# VCO.net
KiCad netlist of a schematic drawn in EAGLE
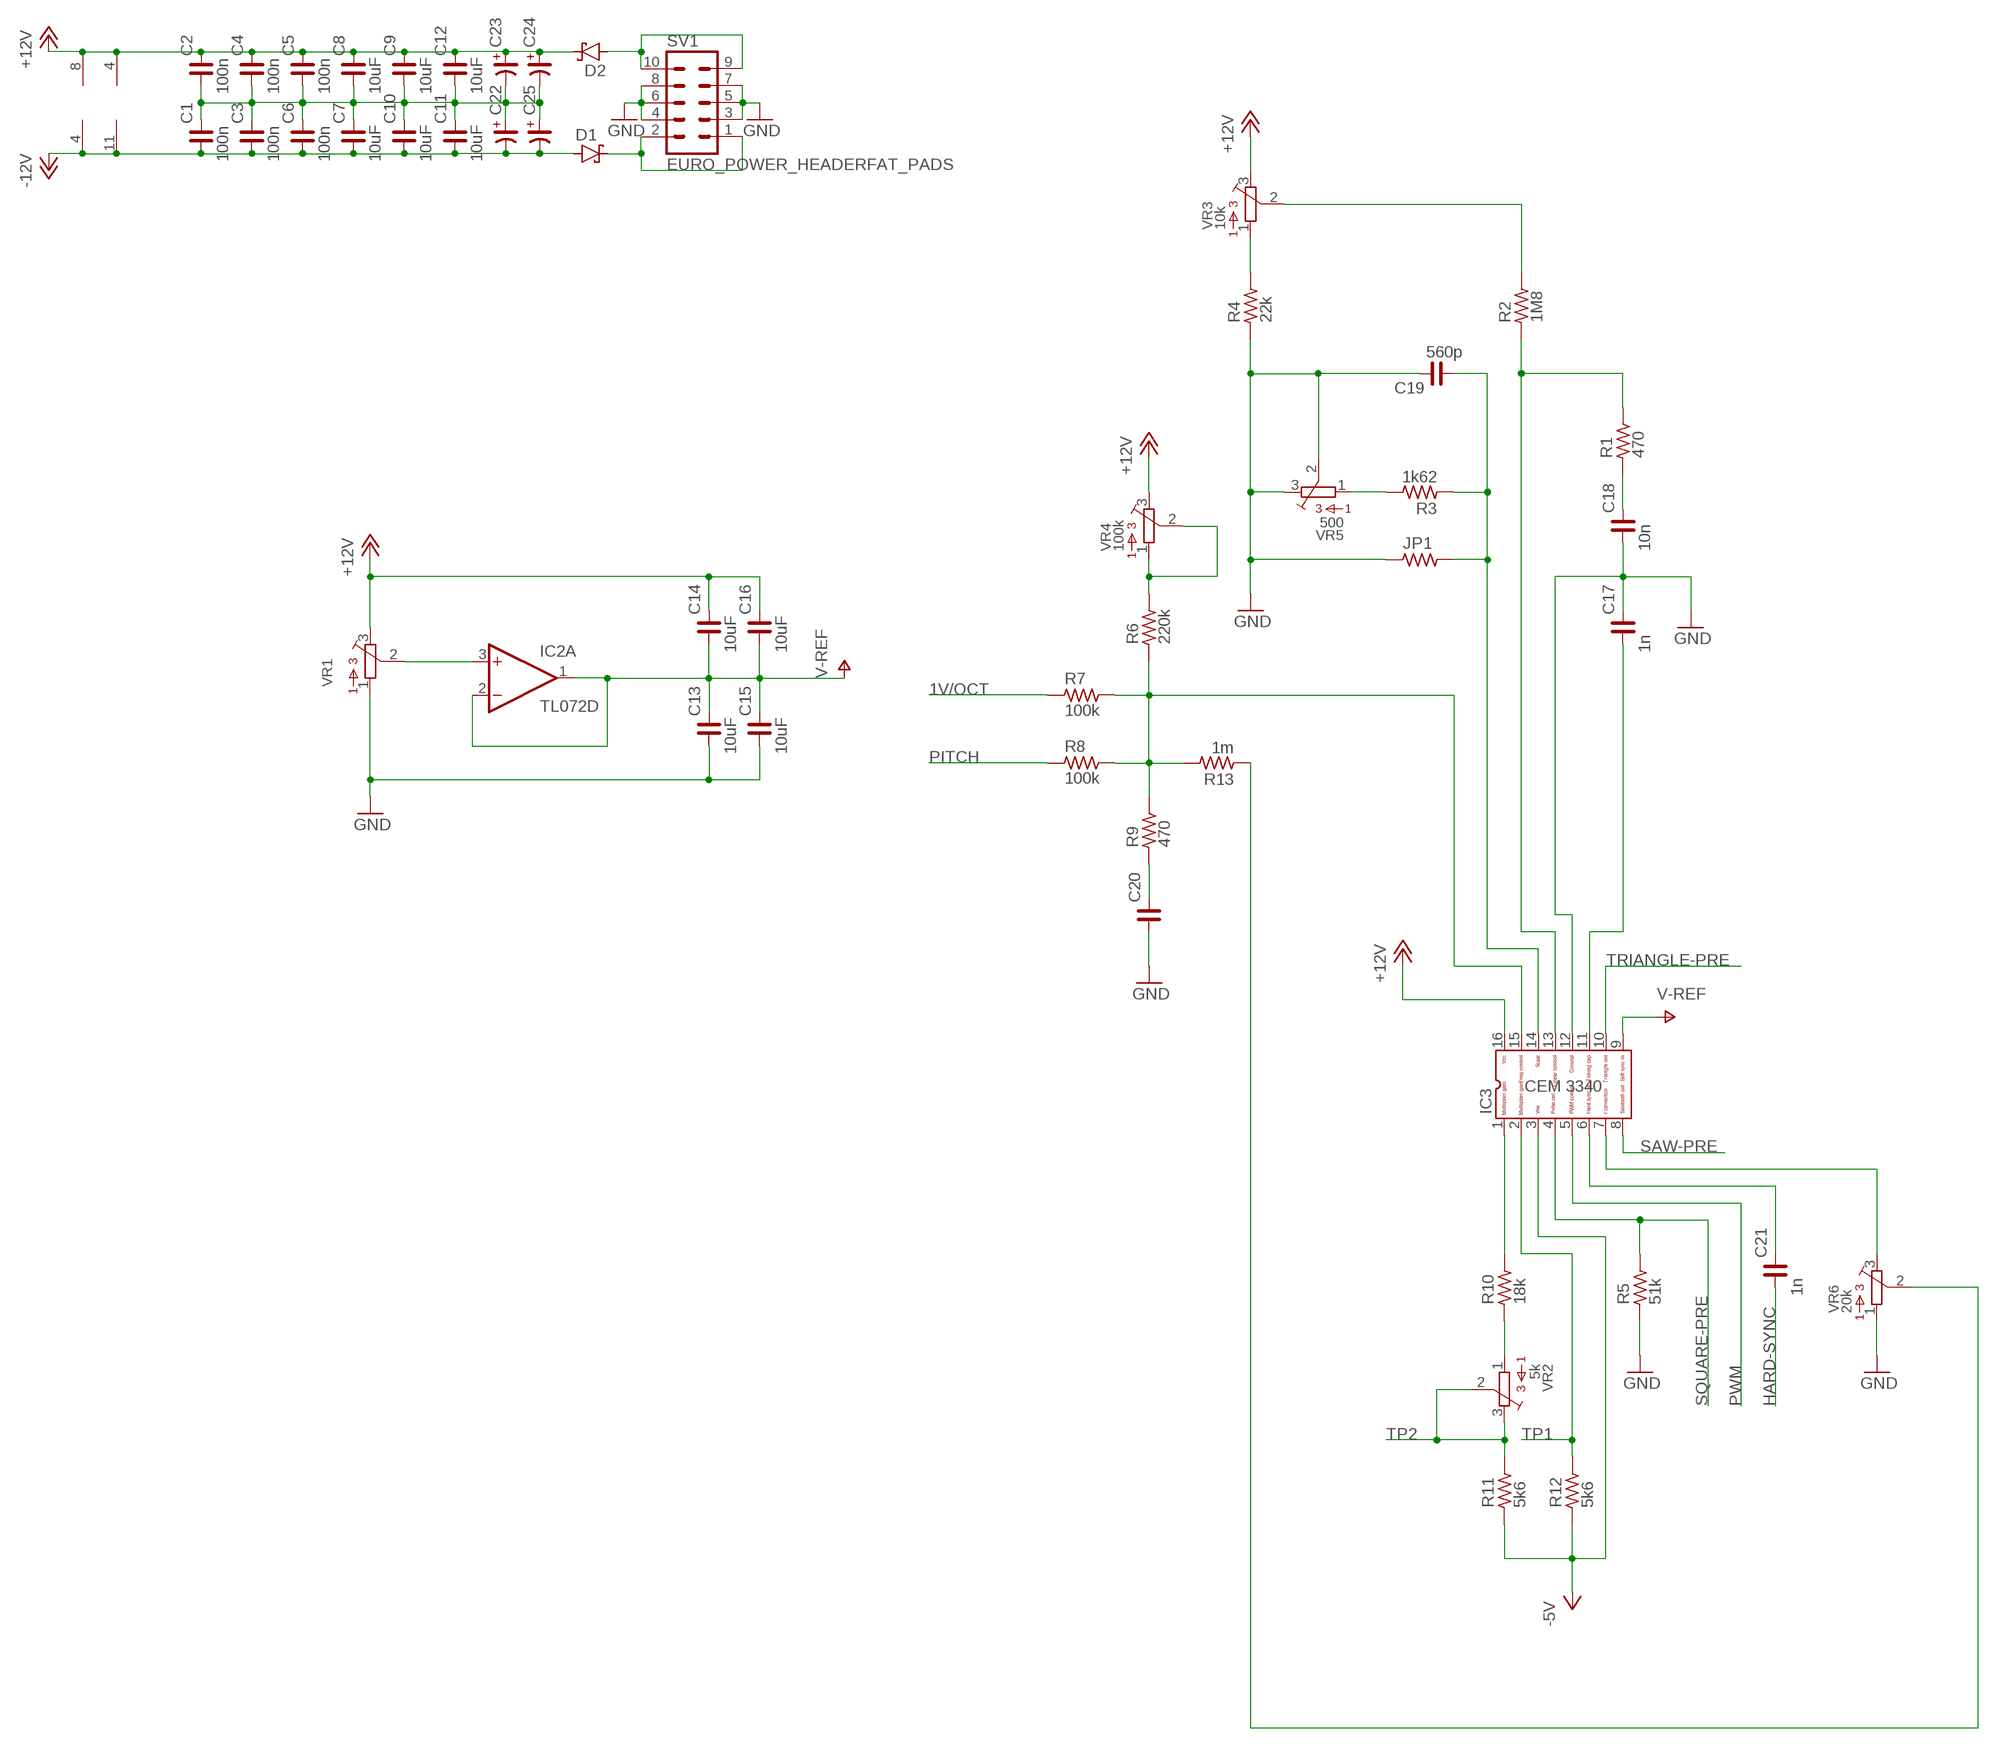
[diagram p0: schematic, sheet 1, part 1 of 2]
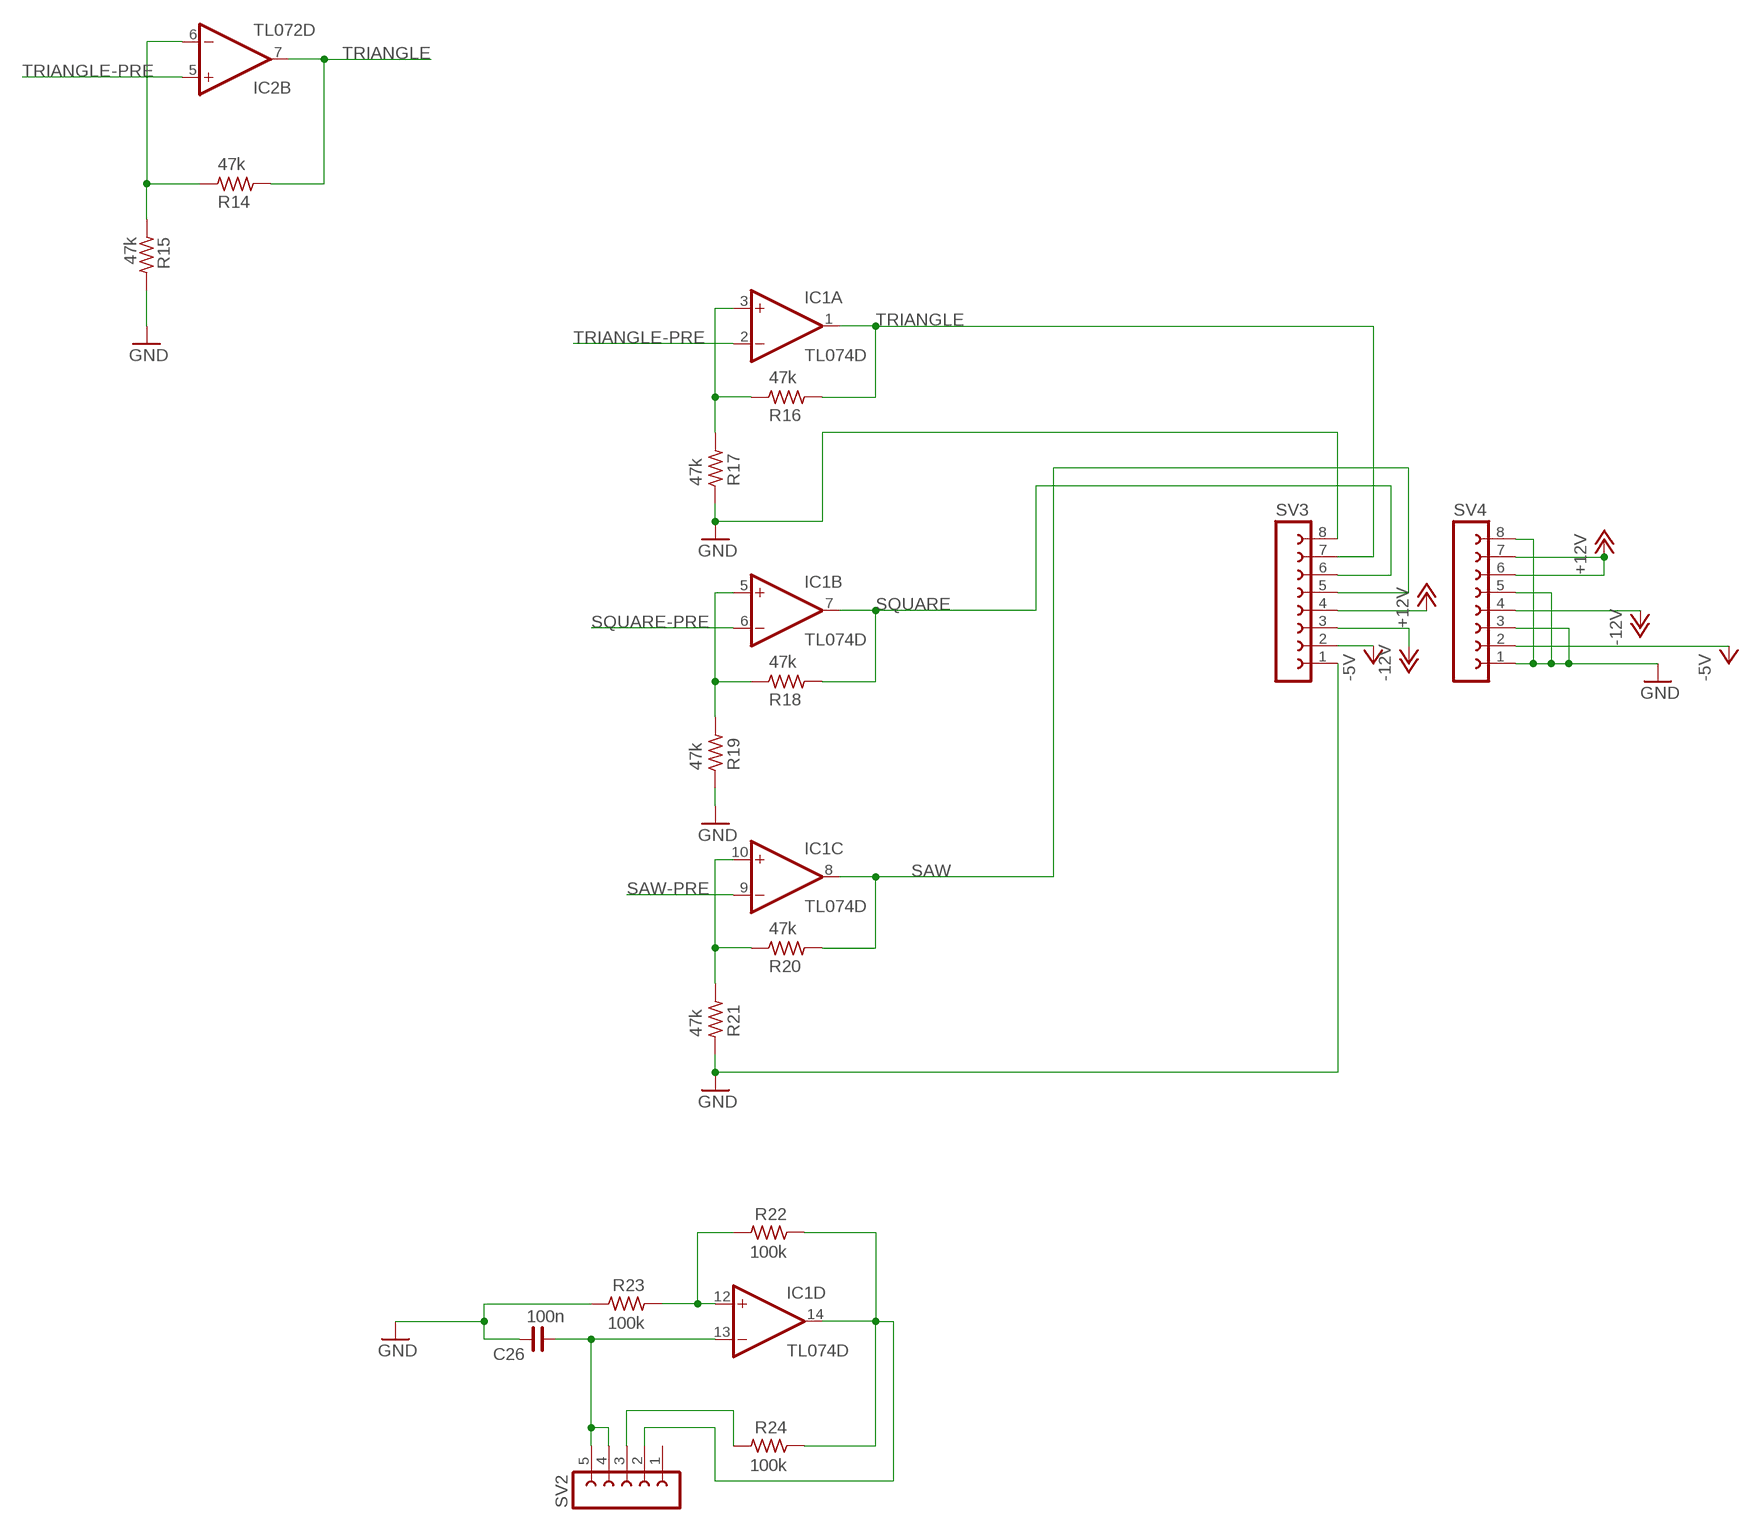
[diagram p1: schematic, sheet 1, part 2 of 2]

(export (version "E")
  (design (tool "Eeschema 10.0.6"))
  (components
    (comp (ref "C1")
      (value "100n")
      (footprint "eagle-import:C0402")
      (libsource (lib "eagle-import") (part "C_0402"))
    )
    (comp (ref "C2")
      (value "100n")
      (footprint "eagle-import:C0402")
      (libsource (lib "eagle-import") (part "C_0402"))
    )
    (comp (ref "C3")
      (value "100n")
      (footprint "eagle-import:C0402")
      (libsource (lib "eagle-import") (part "C_0402"))
    )
    (comp (ref "C4")
      (value "100n")
      (footprint "eagle-import:C0402")
      (libsource (lib "eagle-import") (part "C_0402"))
    )
    (comp (ref "C5")
      (value "100n")
      (footprint "eagle-import:C0402")
      (libsource (lib "eagle-import") (part "C_0402"))
    )
    (comp (ref "C6")
      (value "100n")
      (footprint "eagle-import:C0402")
      (libsource (lib "eagle-import") (part "C_0402"))
    )
    (comp (ref "C7")
      (value "10uF")
      (footprint "eagle-import:C0402")
      (libsource (lib "eagle-import") (part "C_0402"))
    )
    (comp (ref "C8")
      (value "10uF")
      (footprint "eagle-import:C0402")
      (libsource (lib "eagle-import") (part "C_0402"))
    )
    (comp (ref "C9")
      (value "10uF")
      (footprint "eagle-import:C0402")
      (libsource (lib "eagle-import") (part "C_0402"))
    )
    (comp (ref "C10")
      (value "10uF")
      (footprint "eagle-import:C0402")
      (libsource (lib "eagle-import") (part "C_0402"))
    )
    (comp (ref "C11")
      (value "10uF")
      (footprint "eagle-import:C0402")
      (libsource (lib "eagle-import") (part "C_0402"))
    )
    (comp (ref "C12")
      (value "10uF")
      (footprint "eagle-import:C0402")
      (libsource (lib "eagle-import") (part "C_0402"))
    )
    (comp (ref "C13")
      (value "10uF")
      (footprint "eagle-import:C0402")
      (libsource (lib "eagle-import") (part "C_0402"))
    )
    (comp (ref "C14")
      (value "10uF")
      (footprint "eagle-import:C0402")
      (libsource (lib "eagle-import") (part "C_0402"))
    )
    (comp (ref "C15")
      (value "10uF")
      (footprint "eagle-import:C0402")
      (libsource (lib "eagle-import") (part "C_0402"))
    )
    (comp (ref "C16")
      (value "10uF")
      (footprint "eagle-import:C0402")
      (libsource (lib "eagle-import") (part "C_0402"))
    )
    (comp (ref "C17")
      (value "1n")
      (footprint "eagle-import:C0402")
      (libsource (lib "eagle-import") (part "C_0402"))
    )
    (comp (ref "C18")
      (value "10n")
      (footprint "eagle-import:C0402")
      (libsource (lib "eagle-import") (part "C_0402"))
    )
    (comp (ref "C19")
      (value "560p")
      (footprint "eagle-import:C0402")
      (libsource (lib "eagle-import") (part "C_0402"))
    )
    (comp (ref "C20")
      (value "C_0402")
      (footprint "eagle-import:C0402")
      (libsource (lib "eagle-import") (part "C_0402"))
    )
    (comp (ref "C21")
      (value "1n")
      (footprint "eagle-import:C0402")
      (libsource (lib "eagle-import") (part "C_0402"))
    )
    (comp (ref "C22")
      (value "CP_7343")
      (footprint "eagle-import:C7343_T")
      (libsource (lib "eagle-import") (part "CP_7343"))
    )
    (comp (ref "C23")
      (value "CP_7343")
      (footprint "eagle-import:C7343_T")
      (libsource (lib "eagle-import") (part "CP_7343"))
    )
    (comp (ref "C24")
      (value "CP_7343")
      (footprint "eagle-import:C7343_T")
      (libsource (lib "eagle-import") (part "CP_7343"))
    )
    (comp (ref "C25")
      (value "CP_7343")
      (footprint "eagle-import:C7343_T")
      (libsource (lib "eagle-import") (part "CP_7343"))
    )
    (comp (ref "C26")
      (value "100n")
      (footprint "eagle-import:C0402")
      (libsource (lib "eagle-import") (part "C_0402"))
    )
    (comp (ref "D1")
      (value "SCHOTTKY-DIODESMC")
      (footprint "eagle-import:SMC")
      (libsource (lib "eagle-import") (part "SCHOTTKY-DIODESMC"))
    )
    (comp (ref "D2")
      (value "SCHOTTKY-DIODESMC")
      (footprint "eagle-import:SMC")
      (libsource (lib "eagle-import") (part "SCHOTTKY-DIODESMC"))
    )
    (comp (ref "IC1")
      (value "TL074D")
      (footprint "eagle-import:SO14")
      (libsource (lib "eagle-import") (part "TL074D"))
    )
    (comp (ref "IC2")
      (value "TL072D")
      (footprint "eagle-import:SO08")
      (libsource (lib "eagle-import") (part "TL072D"))
    )
    (comp (ref "IC3")
      (value "CEM3340")
      (footprint "eagle-import:DIL16")
      (libsource (lib "eagle-import") (part "CEM3340"))
    )
    (comp (ref "JP1")
      (value "R_0603")
      (footprint "eagle-import:R0603")
      (libsource (lib "eagle-import") (part "R_0603"))
    )
    (comp (ref "R1")
      (value "470")
      (footprint "eagle-import:R0402")
      (libsource (lib "eagle-import") (part "R_0402"))
    )
    (comp (ref "R2")
      (value "1M8")
      (footprint "eagle-import:R0402")
      (libsource (lib "eagle-import") (part "R_0402"))
    )
    (comp (ref "R3")
      (value "1k62")
      (footprint "eagle-import:R0402")
      (libsource (lib "eagle-import") (part "R_0402"))
    )
    (comp (ref "R4")
      (value "22k")
      (footprint "eagle-import:R0402")
      (libsource (lib "eagle-import") (part "R_0402"))
    )
    (comp (ref "R5")
      (value "51k")
      (footprint "eagle-import:R0603")
      (libsource (lib "eagle-import") (part "R_0603"))
    )
    (comp (ref "R6")
      (value "220k")
      (footprint "eagle-import:R0603")
      (libsource (lib "eagle-import") (part "R_0603"))
    )
    (comp (ref "R7")
      (value "100k")
      (footprint "eagle-import:R0603")
      (libsource (lib "eagle-import") (part "R_0603"))
    )
    (comp (ref "R8")
      (value "100k")
      (footprint "eagle-import:R0603")
      (libsource (lib "eagle-import") (part "R_0603"))
    )
    (comp (ref "R9")
      (value "470")
      (footprint "eagle-import:R0603")
      (libsource (lib "eagle-import") (part "R_0603"))
    )
    (comp (ref "R10")
      (value "18k")
      (footprint "eagle-import:R0603")
      (libsource (lib "eagle-import") (part "R_0603"))
    )
    (comp (ref "R11")
      (value "5k6")
      (footprint "eagle-import:R0603")
      (libsource (lib "eagle-import") (part "R_0603"))
    )
    (comp (ref "R12")
      (value "5k6")
      (footprint "eagle-import:R0603")
      (libsource (lib "eagle-import") (part "R_0603"))
    )
    (comp (ref "R13")
      (value "1m")
      (footprint "eagle-import:R0603")
      (libsource (lib "eagle-import") (part "R_0603"))
    )
    (comp (ref "R14")
      (value "47k")
      (footprint "eagle-import:R0603")
      (libsource (lib "eagle-import") (part "R_0603"))
    )
    (comp (ref "R15")
      (value "47k")
      (footprint "eagle-import:R0603")
      (libsource (lib "eagle-import") (part "R_0603"))
    )
    (comp (ref "R16")
      (value "47k")
      (footprint "eagle-import:R0603")
      (libsource (lib "eagle-import") (part "R_0603"))
    )
    (comp (ref "R17")
      (value "47k")
      (footprint "eagle-import:R0603")
      (libsource (lib "eagle-import") (part "R_0603"))
    )
    (comp (ref "R18")
      (value "47k")
      (footprint "eagle-import:R0603")
      (libsource (lib "eagle-import") (part "R_0603"))
    )
    (comp (ref "R19")
      (value "47k")
      (footprint "eagle-import:R0603")
      (libsource (lib "eagle-import") (part "R_0603"))
    )
    (comp (ref "R20")
      (value "47k")
      (footprint "eagle-import:R0603")
      (libsource (lib "eagle-import") (part "R_0603"))
    )
    (comp (ref "R21")
      (value "47k")
      (footprint "eagle-import:R0603")
      (libsource (lib "eagle-import") (part "R_0603"))
    )
    (comp (ref "R22")
      (value "100k")
      (footprint "eagle-import:R0603")
      (libsource (lib "eagle-import") (part "R_0603"))
    )
    (comp (ref "R23")
      (value "100k")
      (footprint "eagle-import:R0603")
      (libsource (lib "eagle-import") (part "R_0603"))
    )
    (comp (ref "R24")
      (value "100k")
      (footprint "eagle-import:R0603")
      (libsource (lib "eagle-import") (part "R_0603"))
    )
    (comp (ref "SV1")
      (value "EURO_POWER_HEADERFAT_PADS")
      (footprint "eagle-import:EURO_PWR_HEADER_FAT")
      (libsource (lib "eagle-import") (part "EURO_POWER_HEADERFAT_PADS"))
    )
    (comp (ref "SV2")
      (value "FE05-1")
      (footprint "eagle-import:FE05-1")
      (libsource (lib "eagle-import") (part "FE05-1"))
    )
    (comp (ref "SV3")
      (value "FE08-1")
      (footprint "eagle-import:FE08")
      (libsource (lib "eagle-import") (part "FE08-1"))
    )
    (comp (ref "SV4")
      (value "FE08-1")
      (footprint "eagle-import:FE08")
      (libsource (lib "eagle-import") (part "FE08-1"))
    )
    (comp (ref "VR1")
      (value "BOURNS_3362P_TRIMMERP")
      (footprint "eagle-import:BOURNS_3362P_TRIMMER")
      (libsource (lib "eagle-import") (part "BOURNS_3362P_TRIMMERP"))
    )
    (comp (ref "VR2")
      (value "5k")
      (footprint "eagle-import:BOURNS_3362P_TRIMMER")
      (libsource (lib "eagle-import") (part "BOURNS_3362P_TRIMMERP"))
    )
    (comp (ref "VR3")
      (value "10k")
      (footprint "eagle-import:BOURNS_3362P_TRIMMER")
      (libsource (lib "eagle-import") (part "BOURNS_3362P_TRIMMERP"))
    )
    (comp (ref "VR4")
      (value "100k")
      (footprint "eagle-import:BOURNS_3362P_TRIMMER")
      (libsource (lib "eagle-import") (part "BOURNS_3362P_TRIMMERP"))
    )
    (comp (ref "VR5")
      (value "500")
      (footprint "eagle-import:BOURNS_3362P_TRIMMER")
      (libsource (lib "eagle-import") (part "BOURNS_3362P_TRIMMERP"))
    )
    (comp (ref "VR6")
      (value "20k")
      (footprint "eagle-import:BOURNS_3362P_TRIMMER")
      (libsource (lib "eagle-import") (part "BOURNS_3362P_TRIMMERP"))
    )
  )
  (nets
    (net (code "1") (name "+12V") (class "Default")
      (node (ref "C12") (pin "2") (pinfunction "2_2") (pintype "passive"))
      (node (ref "C14") (pin "2") (pinfunction "2_2") (pintype "passive"))
      (node (ref "C16") (pin "2") (pinfunction "2_2") (pintype "passive"))
      (node (ref "C2") (pin "2") (pinfunction "2_2") (pintype "passive"))
      (node (ref "C23") (pin "+") (pinfunction "+_+") (pintype "passive"))
      (node (ref "C24") (pin "+") (pinfunction "+_+") (pintype "passive"))
      (node (ref "C4") (pin "2") (pinfunction "2_2") (pintype "passive"))
      (node (ref "C5") (pin "2") (pinfunction "2_2") (pintype "passive"))
      (node (ref "C8") (pin "2") (pinfunction "2_2") (pintype "passive"))
      (node (ref "C9") (pin "2") (pinfunction "2_2") (pintype "passive"))
      (node (ref "D2") (pin "C") (pinfunction "C_C") (pintype "passive"))
      (node (ref "IC1") (pin "4") (pinfunction "V+_4") (pintype "power_in"))
      (node (ref "IC2") (pin "8") (pinfunction "V+_8") (pintype "power_in"))
      (node (ref "IC3") (pin "16") (pinfunction "16_16") (pintype "power_in"))
      (node (ref "SV3") (pin "4") (pinfunction "4_4") (pintype "passive"))
      (node (ref "SV4") (pin "6") (pinfunction "6_6") (pintype "passive"))
      (node (ref "SV4") (pin "7") (pinfunction "7_7") (pintype "passive"))
      (node (ref "VR1") (pin "3") (pinfunction "3_3") (pintype "passive"))
      (node (ref "VR3") (pin "3") (pinfunction "3_3") (pintype "passive"))
      (node (ref "VR4") (pin "3") (pinfunction "3_3") (pintype "passive"))
    )
    (net (code "2") (name "-5V") (class "Default")
      (node (ref "IC3") (pin "3") (pinfunction "3_3") (pintype "power_in"))
      (node (ref "R11") (pin "1") (pinfunction "1_1") (pintype "passive"))
      (node (ref "R12") (pin "1") (pinfunction "1_1") (pintype "passive"))
      (node (ref "SV3") (pin "2") (pinfunction "2_2") (pintype "passive"))
      (node (ref "SV4") (pin "2") (pinfunction "2_2") (pintype "passive"))
    )
    (net (code "3") (name "-12V") (class "Default")
      (node (ref "C1") (pin "1") (pinfunction "1_1") (pintype "passive"))
      (node (ref "C10") (pin "1") (pinfunction "1_1") (pintype "passive"))
      (node (ref "C11") (pin "1") (pinfunction "1_1") (pintype "passive"))
      (node (ref "C22") (pin "-") (pinfunction "-_-") (pintype "passive"))
      (node (ref "C25") (pin "-") (pinfunction "-_-") (pintype "passive"))
      (node (ref "C3") (pin "1") (pinfunction "1_1") (pintype "passive"))
      (node (ref "C6") (pin "1") (pinfunction "1_1") (pintype "passive"))
      (node (ref "C7") (pin "1") (pinfunction "1_1") (pintype "passive"))
      (node (ref "D1") (pin "A") (pinfunction "A_A") (pintype "passive"))
      (node (ref "IC1") (pin "11") (pinfunction "V-_11") (pintype "power_in"))
      (node (ref "IC2") (pin "4") (pinfunction "V-_4") (pintype "power_in"))
      (node (ref "SV3") (pin "3") (pinfunction "3_3") (pintype "passive"))
      (node (ref "SV4") (pin "4") (pinfunction "4_4") (pintype "passive"))
    )
    (net (code "4") (name "/1V{slash}OCT") (class "Default")
      (node (ref "R7") (pin "1") (pinfunction "1_1") (pintype "passive"))
    )
    (net (code "5") (name "/HARD-SYNC") (class "Default")
      (node (ref "C21") (pin "1") (pinfunction "1_1") (pintype "passive"))
    )
    (net (code "6") (name "/PITCH") (class "Default")
      (node (ref "R8") (pin "1") (pinfunction "1_1") (pintype "passive"))
    )
    (net (code "7") (name "/PWM") (class "Default")
      (node (ref "IC3") (pin "5") (pinfunction "5_5") (pintype "input"))
    )
    (net (code "8") (name "/SAW") (class "Default")
      (node (ref "IC1") (pin "8") (pinfunction "OUT_8") (pintype "output"))
      (node (ref "R20") (pin "2") (pinfunction "2_2") (pintype "passive"))
      (node (ref "SV3") (pin "5") (pinfunction "5_5") (pintype "passive"))
    )
    (net (code "9") (name "/SAW-PRE") (class "Default")
      (node (ref "IC1") (pin "9") (pinfunction "-IN_9") (pintype "input"))
      (node (ref "IC3") (pin "8") (pinfunction "8_8") (pintype "output"))
    )
    (net (code "10") (name "/SQUARE") (class "Default")
      (node (ref "IC1") (pin "7") (pinfunction "OUT_7") (pintype "output"))
      (node (ref "R18") (pin "2") (pinfunction "2_2") (pintype "passive"))
      (node (ref "SV3") (pin "6") (pinfunction "6_6") (pintype "passive"))
    )
    (net (code "11") (name "/SQUARE-PRE") (class "Default")
      (node (ref "IC1") (pin "6") (pinfunction "-IN_6") (pintype "input"))
      (node (ref "IC3") (pin "4") (pinfunction "4_4") (pintype "output"))
      (node (ref "R5") (pin "2") (pinfunction "2_2") (pintype "passive"))
    )
    (net (code "12") (name "/TP1") (class "Default")
      (node (ref "IC3") (pin "2") (pinfunction "2_2") (pintype "bidirectional"))
      (node (ref "R12") (pin "2") (pinfunction "2_2") (pintype "passive"))
    )
    (net (code "13") (name "/TP2") (class "Default")
      (node (ref "R11") (pin "2") (pinfunction "2_2") (pintype "passive"))
      (node (ref "VR2") (pin "2") (pinfunction "2_2") (pintype "passive"))
      (node (ref "VR2") (pin "3") (pinfunction "3_3") (pintype "passive"))
    )
    (net (code "14") (name "/TRIANGLE") (class "Default")
      (node (ref "IC1") (pin "1") (pinfunction "OUT_1") (pintype "output"))
      (node (ref "IC2") (pin "7") (pinfunction "OUT_7") (pintype "output"))
      (node (ref "R14") (pin "2") (pinfunction "2_2") (pintype "passive"))
      (node (ref "R16") (pin "2") (pinfunction "2_2") (pintype "passive"))
      (node (ref "SV3") (pin "7") (pinfunction "7_7") (pintype "passive"))
    )
    (net (code "15") (name "/TRIANGLE-PRE") (class "Default")
      (node (ref "IC1") (pin "2") (pinfunction "-IN_2") (pintype "input"))
      (node (ref "IC2") (pin "5") (pinfunction "+IN_5") (pintype "input"))
      (node (ref "IC3") (pin "10") (pinfunction "10_10") (pintype "output"))
    )
    (net (code "16") (name "GND") (class "Default")
      (node (ref "C13") (pin "1") (pinfunction "1_1") (pintype "passive"))
      (node (ref "C15") (pin "1") (pinfunction "1_1") (pintype "passive"))
      (node (ref "C17") (pin "2") (pinfunction "2_2") (pintype "passive"))
      (node (ref "C18") (pin "1") (pinfunction "1_1") (pintype "passive"))
      (node (ref "C19") (pin "2") (pinfunction "2_2") (pintype "passive"))
      (node (ref "C20") (pin "1") (pinfunction "1_1") (pintype "passive"))
      (node (ref "C26") (pin "2") (pinfunction "2_2") (pintype "passive"))
      (node (ref "IC3") (pin "12") (pinfunction "12_12") (pintype "power_in"))
      (node (ref "JP1") (pin "1") (pinfunction "1_1") (pintype "passive"))
      (node (ref "R15") (pin "2") (pinfunction "2_2") (pintype "passive"))
      (node (ref "R17") (pin "1") (pinfunction "1_1") (pintype "passive"))
      (node (ref "R19") (pin "1") (pinfunction "1_1") (pintype "passive"))
      (node (ref "R21") (pin "1") (pinfunction "1_1") (pintype "passive"))
      (node (ref "R23") (pin "2") (pinfunction "2_2") (pintype "passive"))
      (node (ref "R4") (pin "1") (pinfunction "1_1") (pintype "passive"))
      (node (ref "R5") (pin "1") (pinfunction "1_1") (pintype "passive"))
      (node (ref "SV1") (pin "3") (pinfunction "3_3") (pintype "passive"))
      (node (ref "SV1") (pin "4") (pinfunction "4_4") (pintype "passive"))
      (node (ref "SV1") (pin "5") (pinfunction "5_5") (pintype "passive"))
      (node (ref "SV1") (pin "6") (pinfunction "6_6") (pintype "passive"))
      (node (ref "SV1") (pin "7") (pinfunction "7_7") (pintype "passive"))
      (node (ref "SV1") (pin "8") (pinfunction "8_8") (pintype "passive"))
      (node (ref "SV3") (pin "1") (pinfunction "1_1") (pintype "passive"))
      (node (ref "SV3") (pin "8") (pinfunction "8_8") (pintype "passive"))
      (node (ref "SV4") (pin "1") (pinfunction "1_1") (pintype "passive"))
      (node (ref "SV4") (pin "3") (pinfunction "3_3") (pintype "passive"))
      (node (ref "SV4") (pin "5") (pinfunction "5_5") (pintype "passive"))
      (node (ref "SV4") (pin "8") (pinfunction "8_8") (pintype "passive"))
      (node (ref "VR1") (pin "1") (pinfunction "1_1") (pintype "passive"))
      (node (ref "VR5") (pin "2") (pinfunction "2_2") (pintype "passive"))
      (node (ref "VR5") (pin "3") (pinfunction "3_3") (pintype "passive"))
      (node (ref "VR6") (pin "1") (pinfunction "1_1") (pintype "passive"))
    )
    (net (code "17") (name "Net-(C1-Pad2)") (class "Default")
      (node (ref "C1") (pin "2") (pinfunction "2_2") (pintype "passive"))
      (node (ref "C10") (pin "2") (pinfunction "2_2") (pintype "passive"))
      (node (ref "C11") (pin "2") (pinfunction "2_2") (pintype "passive"))
      (node (ref "C12") (pin "1") (pinfunction "1_1") (pintype "passive"))
      (node (ref "C2") (pin "1") (pinfunction "1_1") (pintype "passive"))
      (node (ref "C22") (pin "+") (pinfunction "+_+") (pintype "passive"))
      (node (ref "C23") (pin "-") (pinfunction "-_-") (pintype "passive"))
      (node (ref "C24") (pin "-") (pinfunction "-_-") (pintype "passive"))
      (node (ref "C25") (pin "+") (pinfunction "+_+") (pintype "passive"))
      (node (ref "C3") (pin "2") (pinfunction "2_2") (pintype "passive"))
      (node (ref "C4") (pin "1") (pinfunction "1_1") (pintype "passive"))
      (node (ref "C5") (pin "1") (pinfunction "1_1") (pintype "passive"))
      (node (ref "C6") (pin "2") (pinfunction "2_2") (pintype "passive"))
      (node (ref "C7") (pin "2") (pinfunction "2_2") (pintype "passive"))
      (node (ref "C8") (pin "1") (pinfunction "1_1") (pintype "passive"))
      (node (ref "C9") (pin "1") (pinfunction "1_1") (pintype "passive"))
    )
    (net (code "18") (name "Net-(C17-Pad1)") (class "Default")
      (node (ref "C17") (pin "1") (pinfunction "1_1") (pintype "passive"))
      (node (ref "IC3") (pin "11") (pinfunction "11_11") (pintype "bidirectional"))
    )
    (net (code "19") (name "Net-(C18-Pad2)") (class "Default")
      (node (ref "C18") (pin "2") (pinfunction "2_2") (pintype "passive"))
      (node (ref "R1") (pin "1") (pinfunction "1_1") (pintype "passive"))
    )
    (net (code "20") (name "Net-(C19-Pad1)") (class "Default")
      (node (ref "C19") (pin "1") (pinfunction "1_1") (pintype "passive"))
      (node (ref "IC3") (pin "14") (pinfunction "14_14") (pintype "input"))
      (node (ref "JP1") (pin "2") (pinfunction "2_2") (pintype "passive"))
      (node (ref "R3") (pin "1") (pinfunction "1_1") (pintype "passive"))
    )
    (net (code "21") (name "Net-(C20-Pad2)") (class "Default")
      (node (ref "C20") (pin "2") (pinfunction "2_2") (pintype "passive"))
      (node (ref "R9") (pin "1") (pinfunction "1_1") (pintype "passive"))
    )
    (net (code "22") (name "Net-(C21-Pad2)") (class "Default")
      (node (ref "C21") (pin "2") (pinfunction "2_2") (pintype "passive"))
      (node (ref "IC3") (pin "6") (pinfunction "6_6") (pintype "input"))
    )
    (net (code "23") (name "Net-(D1-PadC)") (class "Default")
      (node (ref "D1") (pin "C") (pinfunction "C_C") (pintype "passive"))
      (node (ref "SV1") (pin "1") (pinfunction "1_1") (pintype "passive"))
      (node (ref "SV1") (pin "2") (pinfunction "2_2") (pintype "passive"))
    )
    (net (code "24") (name "Net-(D2-PadA)") (class "Default")
      (node (ref "D2") (pin "A") (pinfunction "A_A") (pintype "passive"))
      (node (ref "SV1") (pin "10") (pinfunction "10_10") (pintype "passive"))
      (node (ref "SV1") (pin "9") (pinfunction "9_9") (pintype "passive"))
    )
    (net (code "25") (name "Net-(IC1A-+IN)") (class "Default")
      (node (ref "IC1") (pin "3") (pinfunction "+IN_3") (pintype "input"))
      (node (ref "R16") (pin "1") (pinfunction "1_1") (pintype "passive"))
      (node (ref "R17") (pin "2") (pinfunction "2_2") (pintype "passive"))
    )
    (net (code "26") (name "Net-(IC1B-+IN)") (class "Default")
      (node (ref "IC1") (pin "5") (pinfunction "+IN_5") (pintype "input"))
      (node (ref "R18") (pin "1") (pinfunction "1_1") (pintype "passive"))
      (node (ref "R19") (pin "2") (pinfunction "2_2") (pintype "passive"))
    )
    (net (code "27") (name "Net-(IC1C-+IN)") (class "Default")
      (node (ref "IC1") (pin "10") (pinfunction "+IN_10") (pintype "input"))
      (node (ref "R20") (pin "1") (pinfunction "1_1") (pintype "passive"))
      (node (ref "R21") (pin "2") (pinfunction "2_2") (pintype "passive"))
    )
    (net (code "28") (name "Net-(IC1D-+IN)") (class "Default")
      (node (ref "IC1") (pin "12") (pinfunction "+IN_12") (pintype "input"))
      (node (ref "R22") (pin "2") (pinfunction "2_2") (pintype "passive"))
      (node (ref "R23") (pin "1") (pinfunction "1_1") (pintype "passive"))
    )
    (net (code "29") (name "Net-(IC1D--IN)") (class "Default")
      (node (ref "C26") (pin "1") (pinfunction "1_1") (pintype "passive"))
      (node (ref "IC1") (pin "13") (pinfunction "-IN_13") (pintype "input"))
      (node (ref "SV2") (pin "4") (pinfunction "4_4") (pintype "passive"))
      (node (ref "SV2") (pin "5") (pinfunction "5_5") (pintype "passive"))
    )
    (net (code "30") (name "Net-(IC1D-OUT)") (class "Default")
      (node (ref "IC1") (pin "14") (pinfunction "OUT_14") (pintype "output"))
      (node (ref "R22") (pin "1") (pinfunction "1_1") (pintype "passive"))
      (node (ref "R24") (pin "1") (pinfunction "1_1") (pintype "passive"))
      (node (ref "SV2") (pin "2") (pinfunction "2_2") (pintype "passive"))
    )
    (net (code "31") (name "Net-(IC2A-+IN)") (class "Default")
      (node (ref "IC2") (pin "3") (pinfunction "+IN_3") (pintype "input"))
      (node (ref "VR1") (pin "2") (pinfunction "2_2") (pintype "passive"))
    )
    (net (code "32") (name "Net-(IC2B--IN)") (class "Default")
      (node (ref "IC2") (pin "6") (pinfunction "-IN_6") (pintype "input"))
      (node (ref "R14") (pin "1") (pinfunction "1_1") (pintype "passive"))
      (node (ref "R15") (pin "1") (pinfunction "1_1") (pintype "passive"))
    )
    (net (code "33") (name "Net-(IC3-Pad1)") (class "Default")
      (node (ref "IC3") (pin "1") (pinfunction "1_1") (pintype "bidirectional"))
      (node (ref "R10") (pin "2") (pinfunction "2_2") (pintype "passive"))
    )
    (net (code "34") (name "Net-(IC3-Pad7)") (class "Default")
      (node (ref "IC3") (pin "7") (pinfunction "7_7") (pintype "bidirectional"))
      (node (ref "VR6") (pin "3") (pinfunction "3_3") (pintype "passive"))
    )
    (net (code "35") (name "Net-(IC3-Pad13)") (class "Default")
      (node (ref "IC3") (pin "13") (pinfunction "13_13") (pintype "input"))
      (node (ref "R1") (pin "2") (pinfunction "2_2") (pintype "passive"))
      (node (ref "R2") (pin "1") (pinfunction "1_1") (pintype "passive"))
    )
    (net (code "36") (name "Net-(IC3-Pad15)") (class "Default")
      (node (ref "IC3") (pin "15") (pinfunction "15_15") (pintype "input"))
      (node (ref "R13") (pin "2") (pinfunction "2_2") (pintype "passive"))
      (node (ref "R6") (pin "1") (pinfunction "1_1") (pintype "passive"))
      (node (ref "R7") (pin "2") (pinfunction "2_2") (pintype "passive"))
      (node (ref "R8") (pin "2") (pinfunction "2_2") (pintype "passive"))
      (node (ref "R9") (pin "2") (pinfunction "2_2") (pintype "passive"))
    )
    (net (code "37") (name "Net-(R2-Pad2)") (class "Default")
      (node (ref "R2") (pin "2") (pinfunction "2_2") (pintype "passive"))
      (node (ref "VR3") (pin "2") (pinfunction "2_2") (pintype "passive"))
    )
    (net (code "38") (name "Net-(R3-Pad2)") (class "Default")
      (node (ref "R3") (pin "2") (pinfunction "2_2") (pintype "passive"))
      (node (ref "VR5") (pin "1") (pinfunction "1_1") (pintype "passive"))
    )
    (net (code "39") (name "Net-(R4-Pad2)") (class "Default")
      (node (ref "R4") (pin "2") (pinfunction "2_2") (pintype "passive"))
      (node (ref "VR3") (pin "1") (pinfunction "1_1") (pintype "passive"))
    )
    (net (code "40") (name "Net-(R6-Pad2)") (class "Default")
      (node (ref "R6") (pin "2") (pinfunction "2_2") (pintype "passive"))
      (node (ref "VR4") (pin "1") (pinfunction "1_1") (pintype "passive"))
      (node (ref "VR4") (pin "2") (pinfunction "2_2") (pintype "passive"))
    )
    (net (code "41") (name "Net-(R10-Pad1)") (class "Default")
      (node (ref "R10") (pin "1") (pinfunction "1_1") (pintype "passive"))
      (node (ref "VR2") (pin "1") (pinfunction "1_1") (pintype "passive"))
    )
    (net (code "42") (name "Net-(R13-Pad1)") (class "Default")
      (node (ref "R13") (pin "1") (pinfunction "1_1") (pintype "passive"))
      (node (ref "VR6") (pin "2") (pinfunction "2_2") (pintype "passive"))
    )
    (net (code "43") (name "Net-(R24-Pad2)") (class "Default")
      (node (ref "R24") (pin "2") (pinfunction "2_2") (pintype "passive"))
      (node (ref "SV2") (pin "3") (pinfunction "3_3") (pintype "passive"))
    )
    (net (code "44") (name "V-REF") (class "Default")
      (node (ref "C13") (pin "2") (pinfunction "2_2") (pintype "passive"))
      (node (ref "C14") (pin "1") (pinfunction "1_1") (pintype "passive"))
      (node (ref "C15") (pin "2") (pinfunction "2_2") (pintype "passive"))
      (node (ref "C16") (pin "1") (pinfunction "1_1") (pintype "passive"))
      (node (ref "IC2") (pin "1") (pinfunction "OUT_1") (pintype "output"))
      (node (ref "IC2") (pin "2") (pinfunction "-IN_2") (pintype "input"))
      (node (ref "IC3") (pin "9") (pinfunction "9_9") (pintype "input"))
    )
    (net (code "45") (name "unconnected-(SV2-Pad1)") (class "Default")
      (node (ref "SV2") (pin "1") (pinfunction "1_1") (pintype "passive"))
    )
  )
)
